# stm32_board.net
KiCad netlist of a schematic drawn in Altium Designer
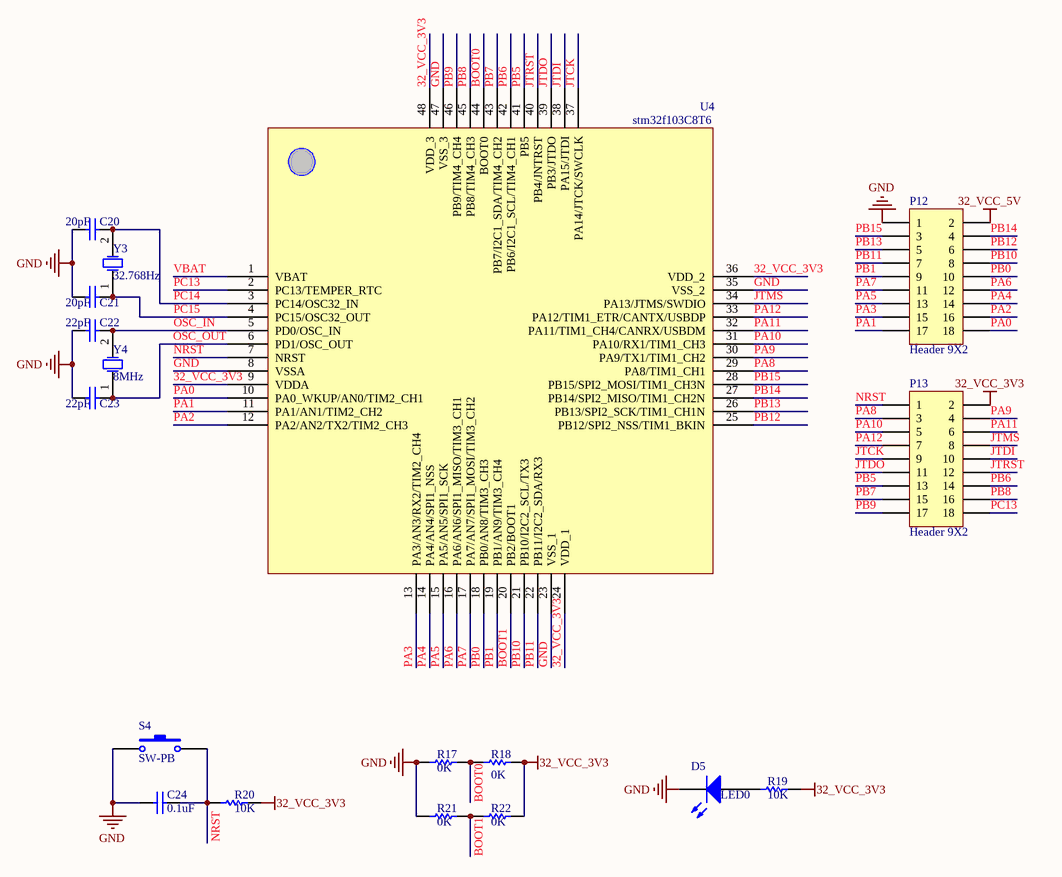
[diagram p0: stm32_board.SchDoc]

(export (version "E")
  (design (tool "Eeschema 10.0.6"))
  (components
    (comp (ref "C20")
      (value "20pF")
      (footprint "6-0805_N")
      (description "Capacitor")
      (fields (field (name "PUBLISHER") "Altium Limited"))
      (libsource (lib "Miscellaneous Devices") (part "Cap"))
    )
    (comp (ref "C21")
      (value "20pF")
      (footprint "6-0805_N")
      (description "Capacitor")
      (fields (field (name "PUBLISHER") "Altium Limited"))
      (libsource (lib "Miscellaneous Devices") (part "Cap"))
    )
    (comp (ref "C22")
      (value "22pF")
      (footprint "6-0805_N")
      (description "Capacitor")
      (fields (field (name "PUBLISHER") "Altium Limited"))
      (libsource (lib "Miscellaneous Devices") (part "Cap"))
    )
    (comp (ref "C23")
      (value "22pF")
      (footprint "6-0805_N")
      (description "Capacitor")
      (fields (field (name "PUBLISHER") "Altium Limited"))
      (libsource (lib "Miscellaneous Devices") (part "Cap"))
    )
    (comp (ref "C24")
      (value "0.1uF")
      (footprint "6-0805_N")
      (description "Capacitor")
      (fields (field (name "PUBLISHER") "Altium Limited"))
      (libsource (lib "Miscellaneous Devices") (part "Cap"))
    )
    (comp (ref "D5")
      (value "LED0")
      (footprint "LED")
      (description "Typical INFRARED GaAs LED")
      (fields (field (name "PUBLISHER") "Altium Limited"))
      (libsource (lib "Miscellaneous Devices") (part "LED0"))
    )
    (comp (ref "P12")
      (value "Header 9X2")
      (footprint "XDR2x9")
      (description "Header, 9-Pin, Dual row")
      (fields (field (name "PUBLISHER") "Altium Limited"))
      (libsource (lib "Miscellaneous Connectors") (part "Header 9X2"))
    )
    (comp (ref "P13")
      (value "Header 9X2")
      (footprint "XDR2x9")
      (description "Header, 9-Pin, Dual row")
      (fields (field (name "PUBLISHER") "Altium Limited"))
      (libsource (lib "Miscellaneous Connectors") (part "Header 9X2"))
    )
    (comp (ref "R17")
      (value "0K")
      (footprint "0402")
      (description "Resistor")
      (fields (field (name "PUBLISHER") "Altium Limited"))
      (libsource (lib "Miscellaneous Devices") (part "Res1"))
    )
    (comp (ref "R18")
      (value "0K")
      (footprint "0402")
      (description "Resistor")
      (fields (field (name "PUBLISHER") "Altium Limited"))
      (libsource (lib "Miscellaneous Devices") (part "Res1"))
    )
    (comp (ref "R19")
      (value "10K")
      (footprint "6-0805_N")
      (description "Resistor")
      (fields (field (name "PUBLISHER") "Altium Limited"))
      (libsource (lib "Miscellaneous Devices") (part "Res1"))
    )
    (comp (ref "R20")
      (value "10K")
      (footprint "6-0805_N")
      (description "Resistor")
      (fields (field (name "PUBLISHER") "Altium Limited"))
      (libsource (lib "Miscellaneous Devices") (part "Res1"))
    )
    (comp (ref "R21")
      (value "0K")
      (footprint "0402")
      (description "Resistor")
      (fields (field (name "PUBLISHER") "Altium Limited"))
      (libsource (lib "Miscellaneous Devices") (part "Res1"))
    )
    (comp (ref "R22")
      (value "0K")
      (footprint "0402")
      (description "Resistor")
      (fields (field (name "PUBLISHER") "Altium Limited"))
      (libsource (lib "Miscellaneous Devices") (part "Res1"))
    )
    (comp (ref "S4")
      (value "SW-PB")
      (footprint "SPST-2")
      (description "Switch")
      (fields (field (name "PUBLISHER") "Altium Limited"))
      (libsource (lib "Miscellaneous Devices") (part "SW-PB"))
    )
    (comp (ref "U4")
      (value "stm32f103C8T6")
      (footprint "LQFP48")
      (libsource (lib "BalanceCar") (part "stm32f103C8T6"))
    )
    (comp (ref "Y3")
      (value "32.768Hz")
      (footprint "HDR1X2")
      (description "Crystal Oscillator")
      (fields (field (name "PUBLISHER") "Altium Limited"))
      (libsource (lib "Miscellaneous Devices") (part "XTAL"))
    )
    (comp (ref "Y4")
      (value "8MHz")
      (footprint "HC-49S")
      (description "Crystal Oscillator")
      (fields (field (name "PUBLISHER") "Altium Limited"))
      (libsource (lib "Miscellaneous Devices") (part "XTAL"))
    )
  )
  (nets
    (net (code "1") (name "/BOOT0") (class "Default")
      (node (ref "R17") (pin "2") (pinfunction "2_2") (pintype "passive"))
      (node (ref "R18") (pin "1") (pinfunction "1_1") (pintype "passive"))
      (node (ref "U4") (pin "44") (pinfunction "BOOT0_44") (pintype "passive"))
    )
    (net (code "2") (name "/BOOT1") (class "Default")
      (node (ref "R21") (pin "2") (pinfunction "2_2") (pintype "passive"))
      (node (ref "R22") (pin "1") (pinfunction "1_1") (pintype "passive"))
      (node (ref "U4") (pin "20") (pinfunction "PB2/BOOT1_20") (pintype "passive"))
    )
    (net (code "3") (name "/JTCK") (class "Default")
      (node (ref "P13") (pin "9") (pinfunction "9_9") (pintype "passive"))
      (node (ref "U4") (pin "37") (pinfunction "PA14/JTCK/SWCLK_37") (pintype "passive"))
    )
    (net (code "4") (name "/JTDI") (class "Default")
      (node (ref "P13") (pin "10") (pinfunction "10_10") (pintype "passive"))
      (node (ref "U4") (pin "38") (pinfunction "PA15/JTDI_38") (pintype "passive"))
    )
    (net (code "5") (name "/JTDO") (class "Default")
      (node (ref "P13") (pin "11") (pinfunction "11_11") (pintype "passive"))
      (node (ref "U4") (pin "39") (pinfunction "PB3/JTDO_39") (pintype "passive"))
    )
    (net (code "6") (name "/JTMS") (class "Default")
      (node (ref "P13") (pin "8") (pinfunction "8_8") (pintype "passive"))
      (node (ref "U4") (pin "34") (pinfunction "PA13/JTMS/SWDIO_34") (pintype "passive"))
    )
    (net (code "7") (name "/JTRST") (class "Default")
      (node (ref "P13") (pin "12") (pinfunction "12_12") (pintype "passive"))
      (node (ref "U4") (pin "40") (pinfunction "PB4/JNTRST_40") (pintype "passive"))
    )
    (net (code "8") (name "/NRST") (class "Default")
      (node (ref "C24") (pin "2") (pinfunction "2_2") (pintype "passive"))
      (node (ref "P13") (pin "1") (pinfunction "1_1") (pintype "passive"))
      (node (ref "R20") (pin "1") (pinfunction "1_1") (pintype "passive"))
      (node (ref "S4") (pin "2") (pinfunction "2_2") (pintype "passive"))
      (node (ref "U4") (pin "7") (pinfunction "NRST_7") (pintype "passive"))
    )
    (net (code "9") (name "/OSC_IN") (class "Default")
      (node (ref "C22") (pin "2") (pinfunction "2_2") (pintype "passive"))
      (node (ref "U4") (pin "5") (pinfunction "PD0/OSC_IN_5") (pintype "passive"))
      (node (ref "Y4") (pin "2") (pinfunction "OSC2_2") (pintype "passive"))
    )
    (net (code "10") (name "/OSC_OUT") (class "Default")
      (node (ref "C23") (pin "2") (pinfunction "2_2") (pintype "passive"))
      (node (ref "U4") (pin "6") (pinfunction "PD1/OSC_OUT_6") (pintype "passive"))
      (node (ref "Y4") (pin "1") (pinfunction "OSC1_1") (pintype "passive"))
    )
    (net (code "11") (name "/PA0") (class "Default")
      (node (ref "P12") (pin "18") (pinfunction "18_18") (pintype "passive"))
      (node (ref "U4") (pin "10") (pinfunction "PA0_WKUP/AN0/TIM2_CH1_10") (pintype "passive"))
    )
    (net (code "12") (name "/PA1") (class "Default")
      (node (ref "P12") (pin "17") (pinfunction "17_17") (pintype "passive"))
      (node (ref "U4") (pin "11") (pinfunction "PA1/AN1/TIM2_CH2_11") (pintype "passive"))
    )
    (net (code "13") (name "/PA2") (class "Default")
      (node (ref "P12") (pin "16") (pinfunction "16_16") (pintype "passive"))
      (node (ref "U4") (pin "12") (pinfunction "PA2/AN2/TX2/TIM2_CH3_12") (pintype "passive"))
    )
    (net (code "14") (name "/PA3") (class "Default")
      (node (ref "P12") (pin "15") (pinfunction "15_15") (pintype "passive"))
      (node (ref "U4") (pin "13") (pinfunction "PA3/AN3/RX2/TIM2_CH4_13") (pintype "passive"))
    )
    (net (code "15") (name "/PA4") (class "Default")
      (node (ref "P12") (pin "14") (pinfunction "14_14") (pintype "passive"))
      (node (ref "U4") (pin "14") (pinfunction "PA4/AN4/SPI1_NSS_14") (pintype "passive"))
    )
    (net (code "16") (name "/PA5") (class "Default")
      (node (ref "P12") (pin "13") (pinfunction "13_13") (pintype "passive"))
      (node (ref "U4") (pin "15") (pinfunction "PA5/AN5/SPI1_SCK_15") (pintype "passive"))
    )
    (net (code "17") (name "/PA6") (class "Default")
      (node (ref "P12") (pin "12") (pinfunction "12_12") (pintype "passive"))
      (node (ref "U4") (pin "16") (pinfunction "PA6/AN6/SPI1_MISO/TIM3_CH1_16") (pintype "passive"))
    )
    (net (code "18") (name "/PA7") (class "Default")
      (node (ref "P12") (pin "11") (pinfunction "11_11") (pintype "passive"))
      (node (ref "U4") (pin "17") (pinfunction "PA7/AN7/SPI1_MOSI/TIM3_CH2_17") (pintype "passive"))
    )
    (net (code "19") (name "/PA8") (class "Default")
      (node (ref "P13") (pin "3") (pinfunction "3_3") (pintype "passive"))
      (node (ref "U4") (pin "29") (pinfunction "PA8/TIM1_CH1_29") (pintype "passive"))
    )
    (net (code "20") (name "/PA9") (class "Default")
      (node (ref "P13") (pin "4") (pinfunction "4_4") (pintype "passive"))
      (node (ref "U4") (pin "30") (pinfunction "PA9/TX1/TIM1_CH2_30") (pintype "passive"))
    )
    (net (code "21") (name "/PA10") (class "Default")
      (node (ref "P13") (pin "5") (pinfunction "5_5") (pintype "passive"))
      (node (ref "U4") (pin "31") (pinfunction "PA10/RX1/TIM1_CH3_31") (pintype "passive"))
    )
    (net (code "22") (name "/PA11") (class "Default")
      (node (ref "P13") (pin "6") (pinfunction "6_6") (pintype "passive"))
      (node (ref "U4") (pin "32") (pinfunction "PA11/TIM1_CH4/CANRX/USBDM_32") (pintype "passive"))
    )
    (net (code "23") (name "/PA12") (class "Default")
      (node (ref "P13") (pin "7") (pinfunction "7_7") (pintype "passive"))
      (node (ref "U4") (pin "33") (pinfunction "PA12/TIM1_ETR/CANTX/USBDP_33") (pintype "passive"))
    )
    (net (code "24") (name "/PB0") (class "Default")
      (node (ref "P12") (pin "10") (pinfunction "10_10") (pintype "passive"))
      (node (ref "U4") (pin "18") (pinfunction "PB0/AN8/TIM3_CH3_18") (pintype "passive"))
    )
    (net (code "25") (name "/PB1") (class "Default")
      (node (ref "P12") (pin "9") (pinfunction "9_9") (pintype "passive"))
      (node (ref "U4") (pin "19") (pinfunction "PB1/AN9/TIM3_CH4_19") (pintype "passive"))
    )
    (net (code "26") (name "/PB5") (class "Default")
      (node (ref "P13") (pin "13") (pinfunction "13_13") (pintype "passive"))
      (node (ref "U4") (pin "41") (pinfunction "PB5_41") (pintype "passive"))
    )
    (net (code "27") (name "/PB6") (class "Default")
      (node (ref "P13") (pin "14") (pinfunction "14_14") (pintype "passive"))
      (node (ref "U4") (pin "42") (pinfunction "PB6/I2C1_SCL/TIM4_CH1_42") (pintype "passive"))
    )
    (net (code "28") (name "/PB7") (class "Default")
      (node (ref "P13") (pin "15") (pinfunction "15_15") (pintype "passive"))
      (node (ref "U4") (pin "43") (pinfunction "PB7/I2C1_SDA/TIM4_CH2_43") (pintype "passive"))
    )
    (net (code "29") (name "/PB8") (class "Default")
      (node (ref "P13") (pin "16") (pinfunction "16_16") (pintype "passive"))
      (node (ref "U4") (pin "45") (pinfunction "PB8/TIM4_CH3_45") (pintype "passive"))
    )
    (net (code "30") (name "/PB9") (class "Default")
      (node (ref "P13") (pin "17") (pinfunction "17_17") (pintype "passive"))
      (node (ref "U4") (pin "46") (pinfunction "PB9/TIM4_CH4_46") (pintype "passive"))
    )
    (net (code "31") (name "/PB10") (class "Default")
      (node (ref "P12") (pin "8") (pinfunction "8_8") (pintype "passive"))
      (node (ref "U4") (pin "21") (pinfunction "PB10/I2C2_SCL/TX3_21") (pintype "passive"))
    )
    (net (code "32") (name "/PB11") (class "Default")
      (node (ref "P12") (pin "7") (pinfunction "7_7") (pintype "passive"))
      (node (ref "U4") (pin "22") (pinfunction "PB11/I2C2_SDA/RX3_22") (pintype "passive"))
    )
    (net (code "33") (name "/PB12") (class "Default")
      (node (ref "P12") (pin "6") (pinfunction "6_6") (pintype "passive"))
      (node (ref "U4") (pin "25") (pinfunction "PB12/SPI2_NSS/TIM1_BKIN_25") (pintype "passive"))
    )
    (net (code "34") (name "/PB13") (class "Default")
      (node (ref "P12") (pin "5") (pinfunction "5_5") (pintype "passive"))
      (node (ref "U4") (pin "26") (pinfunction "PB13/SPI2_SCK/TIM1_CH1N_26") (pintype "passive"))
    )
    (net (code "35") (name "/PB14") (class "Default")
      (node (ref "P12") (pin "4") (pinfunction "4_4") (pintype "passive"))
      (node (ref "U4") (pin "27") (pinfunction "PB14/SPI2_MISO/TIM1_CH2N_27") (pintype "passive"))
    )
    (net (code "36") (name "/PB15") (class "Default")
      (node (ref "P12") (pin "3") (pinfunction "3_3") (pintype "passive"))
      (node (ref "U4") (pin "28") (pinfunction "PB15/SPI2_MOSI/TIM1_CH3N_28") (pintype "passive"))
    )
    (net (code "37") (name "/PC13") (class "Default")
      (node (ref "P13") (pin "18") (pinfunction "18_18") (pintype "passive"))
      (node (ref "U4") (pin "2") (pinfunction "PC13/TEMPER_RTC_2") (pintype "passive"))
    )
    (net (code "38") (name "/PC14") (class "Default")
      (node (ref "C20") (pin "2") (pinfunction "2_2") (pintype "passive"))
      (node (ref "U4") (pin "3") (pinfunction "PC14/OSC32_IN_3") (pintype "passive"))
      (node (ref "Y3") (pin "2") (pinfunction "OSC2_2") (pintype "passive"))
    )
    (net (code "39") (name "/PC15") (class "Default")
      (node (ref "C21") (pin "2") (pinfunction "2_2") (pintype "passive"))
      (node (ref "U4") (pin "4") (pinfunction "PC15/OSC32_OUT_4") (pintype "passive"))
      (node (ref "Y3") (pin "1") (pinfunction "OSC1_1") (pintype "passive"))
    )
    (net (code "40") (name "/VBAT") (class "Default")
      (node (ref "U4") (pin "1") (pinfunction "VBAT_1") (pintype "passive"))
    )
    (net (code "41") (name "32_VCC_3V3") (class "Default")
      (node (ref "P13") (pin "2") (pinfunction "2_2") (pintype "passive"))
      (node (ref "R18") (pin "2") (pinfunction "2_2") (pintype "passive"))
      (node (ref "R19") (pin "2") (pinfunction "2_2") (pintype "passive"))
      (node (ref "R20") (pin "2") (pinfunction "2_2") (pintype "passive"))
      (node (ref "R22") (pin "2") (pinfunction "2_2") (pintype "passive"))
      (node (ref "U4") (pin "24") (pinfunction "VDD_1_24") (pintype "passive"))
      (node (ref "U4") (pin "36") (pinfunction "VDD_2_36") (pintype "passive"))
      (node (ref "U4") (pin "48") (pinfunction "VDD_3_48") (pintype "passive"))
      (node (ref "U4") (pin "9") (pinfunction "VDDA_9") (pintype "passive"))
    )
    (net (code "42") (name "32_VCC_5V") (class "Default")
      (node (ref "P12") (pin "2") (pinfunction "2_2") (pintype "passive"))
    )
    (net (code "43") (name "GND") (class "Default")
      (node (ref "C20") (pin "1") (pinfunction "1_1") (pintype "passive"))
      (node (ref "C21") (pin "1") (pinfunction "1_1") (pintype "passive"))
      (node (ref "C22") (pin "1") (pinfunction "1_1") (pintype "passive"))
      (node (ref "C23") (pin "1") (pinfunction "1_1") (pintype "passive"))
      (node (ref "C24") (pin "1") (pinfunction "1_1") (pintype "passive"))
      (node (ref "D5") (pin "2") (pinfunction "K_2") (pintype "passive"))
      (node (ref "P12") (pin "1") (pinfunction "1_1") (pintype "passive"))
      (node (ref "R17") (pin "1") (pinfunction "1_1") (pintype "passive"))
      (node (ref "R21") (pin "1") (pinfunction "1_1") (pintype "passive"))
      (node (ref "S4") (pin "1") (pinfunction "1_1") (pintype "passive"))
      (node (ref "U4") (pin "23") (pinfunction "VSS_1_23") (pintype "passive"))
      (node (ref "U4") (pin "35") (pinfunction "VSS_2_35") (pintype "passive"))
      (node (ref "U4") (pin "47") (pinfunction "VSS_3_47") (pintype "passive"))
      (node (ref "U4") (pin "8") (pinfunction "VSSA_8") (pintype "passive"))
    )
    (net (code "44") (name "Net-(D5-A)") (class "Default")
      (node (ref "D5") (pin "1") (pinfunction "A_1") (pintype "passive"))
      (node (ref "R19") (pin "1") (pinfunction "1_1") (pintype "passive"))
    )
  )
)
